# quadrature.net
KiCad netlist of a schematic drawn in EAGLE
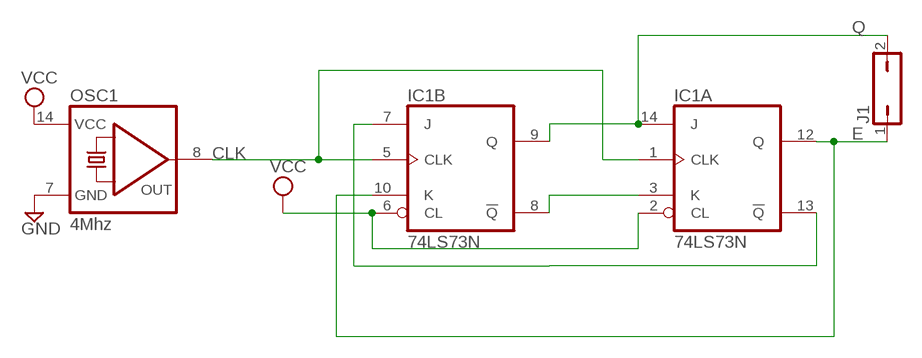
[diagram p0: schematic, sheet 1]

(export (version "E")
  (design (tool "Eeschema 10.0.6"))
  (components
    (comp (ref "IC1")
      (value "74LS73N")
      (footprint "eagle-import:DIL14")
      (libsource (lib "eagle-import") (part "7473NLS"))
    )
    (comp (ref "J1")
      (value "JP1Q")
      (footprint "eagle-import:JP1")
      (libsource (lib "eagle-import") (part "JP1Q"))
    )
    (comp (ref "OSC1")
      (value "4Mhz")
      (footprint "eagle-import:DIL14S")
      (libsource (lib "eagle-import") (part "QG5860"))
    )
  )
  (nets
    (net (code "1") (name "/CLK") (class "Default")
      (node (ref "IC1") (pin "1") (pinfunction "CLK_1") (pintype "input"))
      (node (ref "IC1") (pin "5") (pinfunction "CLK_5") (pintype "input"))
      (node (ref "OSC1") (pin "8") (pinfunction "OUT_8") (pintype "output"))
    )
    (net (code "2") (name "/E") (class "Default")
      (node (ref "IC1") (pin "10") (pinfunction "K_10") (pintype "input"))
      (node (ref "IC1") (pin "12") (pinfunction "Q_12") (pintype "output"))
      (node (ref "J1") (pin "1") (pinfunction "1_1") (pintype "passive"))
    )
    (net (code "3") (name "/Q") (class "Default")
      (node (ref "IC1") (pin "14") (pinfunction "J_14") (pintype "input"))
      (node (ref "IC1") (pin "9") (pinfunction "Q_9") (pintype "output"))
      (node (ref "J1") (pin "2") (pinfunction "2_2") (pintype "passive"))
    )
    (net (code "4") (name "GND") (class "Default")
      (node (ref "OSC1") (pin "7") (pinfunction "GND_7") (pintype "power_in"))
    )
    (net (code "5") (name "Net-(IC1A-K)") (class "Default")
      (node (ref "IC1") (pin "3") (pinfunction "K_3") (pintype "input"))
      (node (ref "IC1") (pin "8") (pinfunction "~{Q}_8") (pintype "output"))
    )
    (net (code "6") (name "Net-(IC1A-~{Q})") (class "Default")
      (node (ref "IC1") (pin "13") (pinfunction "~{Q}_13") (pintype "output"))
      (node (ref "IC1") (pin "7") (pinfunction "J_7") (pintype "input"))
    )
    (net (code "7") (name "VCC") (class "Default")
      (node (ref "IC1") (pin "2") (pinfunction "CL_2") (pintype "input"))
      (node (ref "IC1") (pin "6") (pinfunction "CL_6") (pintype "input"))
      (node (ref "OSC1") (pin "14") (pinfunction "VCC_14") (pintype "power_in"))
    )
  )
)
